# PWR.net
KiCad netlist of a schematic drawn in Altium Designer
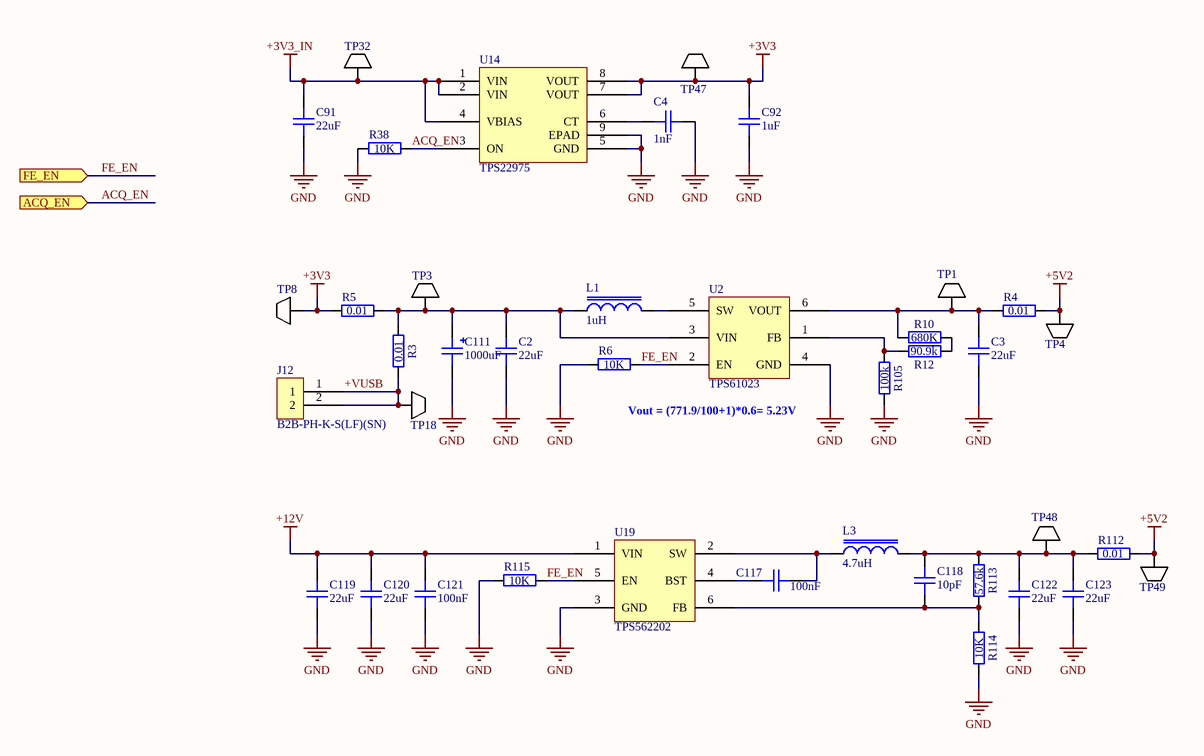
[diagram p0: PWR.SchDoc]

(export (version "E")
  (design (tool "Eeschema 10.0.6"))
  (components
    (comp (ref "C2")
      (value "22uF")
      (footprint "GEN_C_0805")
      (libsource (lib "DSO") (part "CAP 22uF 25V X5R 0805"))
    )
    (comp (ref "C3")
      (value "22uF")
      (footprint "GEN_C_0805")
      (libsource (lib "DSO") (part "CAP 22uF 25V X5R 0805"))
    )
    (comp (ref "C4")
      (value "1nF")
      (footprint "GEN_C_0402")
      (libsource (lib "DSO") (part "CAP 1nF 50V C0G 0402"))
    )
    (comp (ref "C91")
      (value "22uF")
      (footprint "GEN_C_0805")
      (libsource (lib "DSO") (part "CAP 22uF 25V X5R 0805"))
    )
    (comp (ref "C92")
      (value "1uF")
      (footprint "GEN_C_0402")
      (libsource (lib "DSO") (part "CAP 1uF 25V X5R 0402"))
    )
    (comp (ref "C111")
      (value "1000uF")
      (footprint "GEN_C_POLAR_10mm")
      (libsource (lib "DSO") (part "CAP 1000uF 16V 10mm Dia"))
    )
    (comp (ref "C117")
      (value "100nF")
      (footprint "GEN_C_0402")
      (libsource (lib "DSO") (part "CAP 100nF 16V X7R 0402"))
    )
    (comp (ref "C118")
      (value "10pF")
      (footprint "GEN_C_0402")
      (libsource (lib "DSO") (part "CAP 10pF 50V C0G 0402"))
    )
    (comp (ref "C119")
      (value "22uF")
      (footprint "GEN_C_0805")
      (libsource (lib "DSO") (part "CAP 22uF 25V X5R 0805"))
    )
    (comp (ref "C120")
      (value "22uF")
      (footprint "GEN_C_0805")
      (libsource (lib "DSO") (part "CAP 22uF 25V X5R 0805"))
    )
    (comp (ref "C121")
      (value "100nF")
      (footprint "GEN_C_0402")
      (libsource (lib "DSO") (part "CAP 100nF 16V X7R 0402"))
    )
    (comp (ref "C122")
      (value "22uF")
      (footprint "GEN_C_0805")
      (libsource (lib "DSO") (part "CAP 22uF 25V X5R 0805"))
    )
    (comp (ref "C123")
      (value "22uF")
      (footprint "GEN_C_0805")
      (libsource (lib "DSO") (part "CAP 22uF 25V X5R 0805"))
    )
    (comp (ref "J12")
      (value "B2B-PH-K-S(LF)(SN)")
      (footprint "JST_B2B-PH-K-S(LF)(SN)")
      (libsource (lib "DSO") (part "CONN JST PH 2 Pin TH"))
    )
    (comp (ref "L1")
      (value "1uH")
      (footprint "GEN_L_1210")
      (libsource (lib "DSO") (part "IND 1uH 3.1A 45 MOHM 1210"))
    )
    (comp (ref "L3")
      (value "4.7uH")
      (footprint "TY_IND_NRS5030")
      (libsource (lib "DSO") (part "IND 4.7uH 2.6A 35 MOHM SMD"))
    )
    (comp (ref "R3")
      (value "0.01")
      (footprint "GEN_R_0603")
      (fields (field (name "TOLERANCE") "1%"))
      (libsource (lib "DSO") (part "RES 0.01 OHM 1% 1/4W 0603"))
    )
    (comp (ref "R4")
      (value "0.01")
      (footprint "GEN_R_0603")
      (fields (field (name "TOLERANCE") "1%"))
      (libsource (lib "") (part "RES 0.01 OHM 1% 1/4W 0603_1"))
    )
    (comp (ref "R5")
      (value "0.01")
      (footprint "GEN_R_0603")
      (fields (field (name "TOLERANCE") "1%"))
      (libsource (lib "") (part "RES 0.01 OHM 1% 1/4W 0603_2"))
    )
    (comp (ref "R6")
      (value "10K")
      (footprint "GEN_R_0402")
      (fields (field (name "TOLERANCE") "1%"))
      (libsource (lib "") (part "RES 10K OHM 1% 1/10W 0402_1"))
    )
    (comp (ref "R10")
      (value "680K")
      (footprint "GEN_R_0402")
      (fields
        (field (name "TOLERANCE") "1%")
        (field (name "MANUFACTURER") "Yageo")
        (field (name "MANUFACTURER PART NUMBER") "RC0402FR-07681KL")
      )
      (libsource (lib "DSO") (part "RES 680K OHM 1% 1/16W 0402"))
    )
    (comp (ref "R12")
      (value "90.9k")
      (footprint "GEN_R_0402")
      (fields (field (name "TOLERANCE") "1%"))
      (libsource (lib "DSO") (part "RES 90.9K OHM 1% 1/16W 0402"))
    )
    (comp (ref "R38")
      (value "10K")
      (footprint "GEN_R_0402")
      (fields (field (name "TOLERANCE") "1%"))
      (libsource (lib "DSO") (part "RES 10K OHM 1% 1/10W 0402"))
    )
    (comp (ref "R105")
      (value "100k")
      (footprint "GEN_R_0402")
      (fields (field (name "TOLERANCE") "1%"))
      (libsource (lib "DSO") (part "RES 100K OHM 1% 1/10W 0402"))
    )
    (comp (ref "R112")
      (value "0.01")
      (footprint "GEN_R_0603")
      (fields (field (name "TOLERANCE") "1%"))
      (libsource (lib "") (part "RES 0.01 OHM 1% 1/4W 0603_1"))
    )
    (comp (ref "R113")
      (value "57.6k")
      (footprint "GEN_R_0402")
      (fields (field (name "TOLERANCE") "1%"))
      (libsource (lib "DSO") (part "RES 57.6K OHM 1% 1/16W 0402"))
    )
    (comp (ref "R114")
      (value "10K")
      (footprint "GEN_R_0402")
      (fields (field (name "TOLERANCE") "1%"))
      (libsource (lib "DSO") (part "RES 10K OHM 1% 1/10W 0402"))
    )
    (comp (ref "R115")
      (value "10K")
      (footprint "GEN_R_0402")
      (fields (field (name "TOLERANCE") "1%"))
      (libsource (lib "") (part "RES 10K OHM 1% 1/10W 0402_1"))
    )
    (comp (ref "TP1") (value "5015") (footprint "KEY_5015") (libsource (lib "DSO") (part "TP KEYSTONE 5015")))
    (comp (ref "TP3") (value "5015") (footprint "KEY_5015") (libsource (lib "DSO") (part "TP KEYSTONE 5015")))
    (comp (ref "TP4") (value "5015") (footprint "KEY_5015") (libsource (lib "DSO") (part "TP KEYSTONE 5015")))
    (comp (ref "TP8") (value "5015") (footprint "KEY_5015") (libsource (lib "DSO") (part "TP KEYSTONE 5015")))
    (comp (ref "TP18")
      (value "5015")
      (footprint "KEY_5015")
      (libsource (lib "DSO") (part "TP KEYSTONE 5015"))
    )
    (comp (ref "TP32")
      (value "5015")
      (footprint "KEY_5015")
      (libsource (lib "DSO") (part "TP KEYSTONE 5015"))
    )
    (comp (ref "TP47")
      (value "5015")
      (footprint "KEY_5015")
      (libsource (lib "DSO") (part "TP KEYSTONE 5015"))
    )
    (comp (ref "TP48")
      (value "5015")
      (footprint "KEY_5015")
      (libsource (lib "DSO") (part "TP KEYSTONE 5015"))
    )
    (comp (ref "TP49")
      (value "5015")
      (footprint "KEY_5015")
      (libsource (lib "DSO") (part "TP KEYSTONE 5015"))
    )
    (comp (ref "U2")
      (value "TPS61023")
      (footprint "TI_SOT563_DRL0006A")
      (libsource (lib "DSO") (part "IC BOOST TPS61023"))
    )
    (comp (ref "U14")
      (value "TPS22975")
      (footprint "TI_WSON8_DSG0008A")
      (libsource (lib "DSO") (part "IC SWITCH LOAD TPS22975"))
    )
    (comp (ref "U19")
      (value "TPS562202")
      (footprint "TI_SOT563_DRL0006A")
      (libsource (lib "DSO") (part "IC BUCK TPS562202"))
    )
  )
  (nets
    (net (code "1") (name "+3V3") (class "Default")
      (node (ref "C92") (pin "2") (pinfunction "2_2") (pintype "passive"))
      (node (ref "R5") (pin "2") (pinfunction "2_2") (pintype "passive"))
      (node (ref "TP47") (pin "1") (pinfunction "1_1") (pintype "passive"))
      (node (ref "TP8") (pin "1") (pinfunction "1_1") (pintype "passive"))
      (node (ref "U14") (pin "7") (pinfunction "VOUT_7") (pintype "passive"))
      (node (ref "U14") (pin "8") (pinfunction "VOUT_8") (pintype "passive"))
    )
    (net (code "2") (name "+3V3_IN") (class "Default")
      (node (ref "C91") (pin "2") (pinfunction "2_2") (pintype "passive"))
      (node (ref "TP32") (pin "1") (pinfunction "1_1") (pintype "passive"))
      (node (ref "U14") (pin "1") (pinfunction "VIN_1") (pintype "passive"))
      (node (ref "U14") (pin "2") (pinfunction "VIN_2") (pintype "passive"))
      (node (ref "U14") (pin "4") (pinfunction "VBIAS_4") (pintype "passive"))
    )
    (net (code "3") (name "+5V2") (class "Default")
      (node (ref "R112") (pin "2") (pinfunction "2_2") (pintype "passive"))
      (node (ref "R4") (pin "2") (pinfunction "2_2") (pintype "passive"))
      (node (ref "TP4") (pin "1") (pinfunction "1_1") (pintype "passive"))
      (node (ref "TP49") (pin "1") (pinfunction "1_1") (pintype "passive"))
    )
    (net (code "4") (name "+12V") (class "Default")
      (node (ref "C119") (pin "2") (pinfunction "2_2") (pintype "passive"))
      (node (ref "C120") (pin "2") (pinfunction "2_2") (pintype "passive"))
      (node (ref "C121") (pin "1") (pinfunction "1_1") (pintype "passive"))
      (node (ref "U19") (pin "1") (pinfunction "VIN_1") (pintype "power_in"))
    )
    (net (code "5") (name "/+VUSB") (class "Default")
      (node (ref "J12") (pin "1") (pinfunction "1_1") (pintype "passive"))
      (node (ref "J12") (pin "2") (pinfunction "2_2") (pintype "passive"))
      (node (ref "R3") (pin "2") (pinfunction "2_2") (pintype "passive"))
      (node (ref "TP18") (pin "1") (pinfunction "1_1") (pintype "passive"))
    )
    (net (code "6") (name "/ACQ_EN") (class "Default")
      (node (ref "R38") (pin "2") (pinfunction "2_2") (pintype "passive"))
      (node (ref "U14") (pin "3") (pinfunction "ON_3") (pintype "passive"))
    )
    (net (code "7") (name "/FE_EN") (class "Default")
      (node (ref "R115") (pin "1") (pinfunction "1_1") (pintype "passive"))
      (node (ref "R6") (pin "1") (pinfunction "1_1") (pintype "passive"))
      (node (ref "U19") (pin "5") (pinfunction "EN_5") (pintype "passive"))
      (node (ref "U2") (pin "2") (pinfunction "EN_2") (pintype "passive"))
    )
    (net (code "8") (name "GND") (class "Default")
      (node (ref "C111") (pin "2") (pinfunction "2_2") (pintype "passive"))
      (node (ref "C119") (pin "1") (pinfunction "1_1") (pintype "passive"))
      (node (ref "C120") (pin "1") (pinfunction "1_1") (pintype "passive"))
      (node (ref "C121") (pin "2") (pinfunction "2_2") (pintype "passive"))
      (node (ref "C122") (pin "1") (pinfunction "1_1") (pintype "passive"))
      (node (ref "C123") (pin "1") (pinfunction "1_1") (pintype "passive"))
      (node (ref "C2") (pin "1") (pinfunction "1_1") (pintype "passive"))
      (node (ref "C3") (pin "1") (pinfunction "1_1") (pintype "passive"))
      (node (ref "C4") (pin "1") (pinfunction "1_1") (pintype "passive"))
      (node (ref "C91") (pin "1") (pinfunction "1_1") (pintype "passive"))
      (node (ref "C92") (pin "1") (pinfunction "1_1") (pintype "passive"))
      (node (ref "R105") (pin "1") (pinfunction "1_1") (pintype "passive"))
      (node (ref "R114") (pin "1") (pinfunction "1_1") (pintype "passive"))
      (node (ref "R115") (pin "2") (pinfunction "2_2") (pintype "passive"))
      (node (ref "R38") (pin "1") (pinfunction "1_1") (pintype "passive"))
      (node (ref "R6") (pin "2") (pinfunction "2_2") (pintype "passive"))
      (node (ref "U14") (pin "5") (pinfunction "GND_5") (pintype "passive"))
      (node (ref "U14") (pin "9") (pinfunction "EPAD_9") (pintype "passive"))
      (node (ref "U19") (pin "3") (pinfunction "GND_3") (pintype "power_in"))
      (node (ref "U2") (pin "4") (pinfunction "GND_4") (pintype "power_in"))
    )
    (net (code "9") (name "Net-(C118-Pad2)") (class "Default")
      (node (ref "C118") (pin "2") (pinfunction "2_2") (pintype "passive"))
      (node (ref "C122") (pin "2") (pinfunction "2_2") (pintype "passive"))
      (node (ref "C123") (pin "2") (pinfunction "2_2") (pintype "passive"))
      (node (ref "L3") (pin "2") (pinfunction "2_2") (pintype "passive"))
      (node (ref "R112") (pin "1") (pinfunction "1_1") (pintype "passive"))
      (node (ref "R113") (pin "2") (pinfunction "2_2") (pintype "passive"))
      (node (ref "TP48") (pin "1") (pinfunction "1_1") (pintype "passive"))
    )
    (net (code "10") (name "Net-(R10-Pad1)") (class "Default")
      (node (ref "R10") (pin "1") (pinfunction "1_1") (pintype "passive"))
      (node (ref "R12") (pin "2") (pinfunction "2_2") (pintype "passive"))
    )
    (net (code "11") (name "Net-(U2-FB)") (class "Default")
      (node (ref "R105") (pin "2") (pinfunction "2_2") (pintype "passive"))
      (node (ref "R12") (pin "1") (pinfunction "1_1") (pintype "passive"))
      (node (ref "U2") (pin "1") (pinfunction "FB_1") (pintype "passive"))
    )
    (net (code "12") (name "Net-(U2-SW)") (class "Default")
      (node (ref "L1") (pin "2") (pinfunction "2_2") (pintype "passive"))
      (node (ref "U2") (pin "5") (pinfunction "SW_5") (pintype "passive"))
    )
    (net (code "13") (name "Net-(U2-VIN)") (class "Default")
      (node (ref "C111") (pin "1") (pinfunction "1_1") (pintype "passive"))
      (node (ref "C2") (pin "2") (pinfunction "2_2") (pintype "passive"))
      (node (ref "L1") (pin "1") (pinfunction "1_1") (pintype "passive"))
      (node (ref "R3") (pin "1") (pinfunction "1_1") (pintype "passive"))
      (node (ref "R5") (pin "1") (pinfunction "1_1") (pintype "passive"))
      (node (ref "TP3") (pin "1") (pinfunction "1_1") (pintype "passive"))
      (node (ref "U2") (pin "3") (pinfunction "VIN_3") (pintype "power_in"))
    )
    (net (code "14") (name "Net-(U2-VOUT)") (class "Default")
      (node (ref "C3") (pin "2") (pinfunction "2_2") (pintype "passive"))
      (node (ref "R10") (pin "2") (pinfunction "2_2") (pintype "passive"))
      (node (ref "R4") (pin "1") (pinfunction "1_1") (pintype "passive"))
      (node (ref "TP1") (pin "1") (pinfunction "1_1") (pintype "passive"))
      (node (ref "U2") (pin "6") (pinfunction "VOUT_6") (pintype "passive"))
    )
    (net (code "15") (name "Net-(U14-CT)") (class "Default")
      (node (ref "C4") (pin "2") (pinfunction "2_2") (pintype "passive"))
      (node (ref "U14") (pin "6") (pinfunction "CT_6") (pintype "passive"))
    )
    (net (code "16") (name "Net-(U19-BST)") (class "Default")
      (node (ref "C117") (pin "2") (pinfunction "2_2") (pintype "passive"))
      (node (ref "U19") (pin "4") (pinfunction "BST_4") (pintype "passive"))
    )
    (net (code "17") (name "Net-(U19-FB)") (class "Default")
      (node (ref "C118") (pin "1") (pinfunction "1_1") (pintype "passive"))
      (node (ref "R113") (pin "1") (pinfunction "1_1") (pintype "passive"))
      (node (ref "R114") (pin "2") (pinfunction "2_2") (pintype "passive"))
      (node (ref "U19") (pin "6") (pinfunction "FB_6") (pintype "passive"))
    )
    (net (code "18") (name "Net-(U19-SW)") (class "Default")
      (node (ref "C117") (pin "1") (pinfunction "1_1") (pintype "passive"))
      (node (ref "L3") (pin "1") (pinfunction "1_1") (pintype "passive"))
      (node (ref "U19") (pin "2") (pinfunction "SW_2") (pintype "passive"))
    )
  )
)
